# cir23.net
KiCad netlist of a schematic drawn in EAGLE
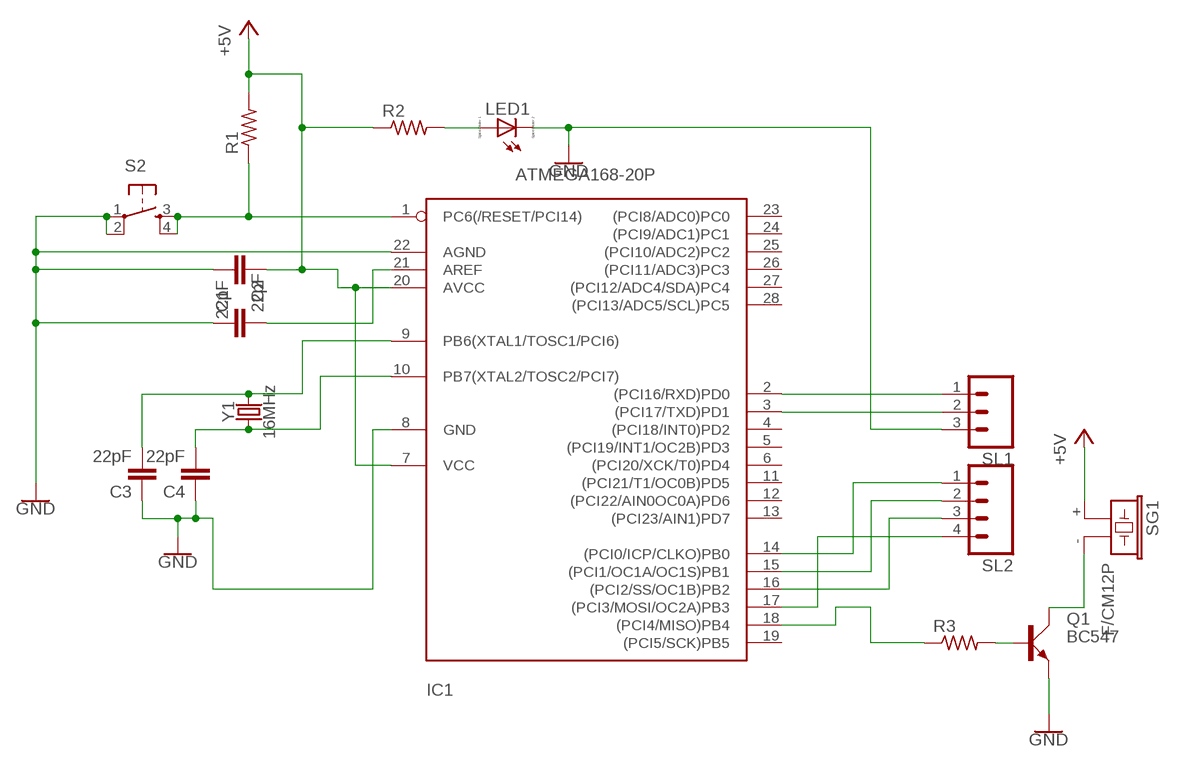
[diagram p0: schematic, sheet 1]

(export (version "E")
  (design (tool "Eeschema 10.0.6"))
  (components
    (comp (ref "C1")
      (value "22pF")
      (footprint "eagle-import:CAP-PTH-2.54")
      (libsource (lib "eagle-import") (part "22PF-PTH-2.54MM-200V-5%"))
    )
    (comp (ref "C2")
      (value "22pF")
      (footprint "eagle-import:CAP-PTH-2.54")
      (libsource (lib "eagle-import") (part "22PF-PTH-2.54MM-200V-5%"))
    )
    (comp (ref "C3")
      (value "22pF")
      (footprint "eagle-import:CAP-PTH-2.54")
      (libsource (lib "eagle-import") (part "22PF-PTH-2.54MM-200V-5%"))
    )
    (comp (ref "C4")
      (value "22pF")
      (footprint "eagle-import:CAP-PTH-2.54")
      (libsource (lib "eagle-import") (part "22PF-PTH-2.54MM-200V-5%"))
    )
    (comp (ref "IC1")
      (value "ATMEGA168-20P")
      (footprint "eagle-import:DIL28-3")
      (libsource (lib "eagle-import") (part "ATMEGA168P-20"))
    )
    (comp (ref "LED1")
      (value "LED_ELD260")
      (footprint "eagle-import:LED_LD260")
      (libsource (lib "eagle-import") (part "LED_ELD260"))
    )
    (comp (ref "Q1")
      (value "BC547")
      (footprint "eagle-import:SOT54A")
      (libsource (lib "eagle-import") (part "BC547"))
    )
    (comp (ref "R1")
      (value "R-US_0204/7")
      (footprint "eagle-import:0204_7")
      (libsource (lib "eagle-import") (part "R-US_0204/7"))
    )
    (comp (ref "R2")
      (value "R-US_0204/7")
      (footprint "eagle-import:0204_7")
      (libsource (lib "eagle-import") (part "R-US_0204/7"))
    )
    (comp (ref "R3")
      (value "R-US_0204/7")
      (footprint "eagle-import:0204_7")
      (libsource (lib "eagle-import") (part "R-US_0204/7"))
    )
    (comp (ref "S2")
      (value "TAC_SWITCHPTH")
      (footprint "eagle-import:TACTILE-PTH")
      (libsource (lib "eagle-import") (part "TAC_SWITCHPTH"))
    )
    (comp (ref "SG1")
      (value "F/CM12P")
      (footprint "eagle-import:F_CM12P")
      (libsource (lib "eagle-import") (part "F/CM12P"))
    )
    (comp (ref "SL1")
      (value "MA03")
      (footprint "eagle-import:03P")
      (libsource (lib "eagle-import") (part "MA03"))
    )
    (comp (ref "SL2")
      (value "MA04")
      (footprint "eagle-import:04PA")
      (libsource (lib "eagle-import") (part "MA04"))
    )
    (comp (ref "Y1")
      (value "16MHz")
      (footprint "eagle-import:HC49US")
      (libsource (lib "eagle-import") (part "CRYSTAL-16MHZPTH-HC49US"))
    )
  )
  (nets
    (net (code "1") (name "+5V") (class "Default")
      (node (ref "C2") (pin "1") (pinfunction "1_1") (pintype "passive"))
      (node (ref "IC1") (pin "20") (pinfunction "AVCC_20") (pintype "bidirectional"))
      (node (ref "IC1") (pin "7") (pinfunction "VCC_7") (pintype "bidirectional"))
      (node (ref "R1") (pin "2") (pinfunction "2_2") (pintype "passive"))
      (node (ref "R2") (pin "1") (pinfunction "1_1") (pintype "passive"))
      (node (ref "SG1") (pin "+") (pinfunction "1_+") (pintype "passive"))
    )
    (net (code "2") (name "GND") (class "Default")
      (node (ref "C1") (pin "1") (pinfunction "1_1") (pintype "passive"))
      (node (ref "C2") (pin "2") (pinfunction "2_2") (pintype "passive"))
      (node (ref "C3") (pin "1") (pinfunction "1_1") (pintype "passive"))
      (node (ref "C4") (pin "1") (pinfunction "1_1") (pintype "passive"))
      (node (ref "IC1") (pin "22") (pinfunction "AGND_22") (pintype "bidirectional"))
      (node (ref "IC1") (pin "8") (pinfunction "GND_8") (pintype "bidirectional"))
      (node (ref "LED1") (pin "K") (pinfunction "C_K") (pintype "passive"))
      (node (ref "Q1") (pin "E") (pinfunction "E_E") (pintype "passive"))
      (node (ref "S2") (pin "1") (pinfunction "1_1") (pintype "passive"))
      (node (ref "S2") (pin "2") (pinfunction "2_2") (pintype "passive"))
      (node (ref "SL1") (pin "3") (pinfunction "3_3") (pintype "passive"))
    )
    (net (code "3") (name "Net-(IC1-(PCI0{slash}ICP{slash}CLKO)PB0)") (class "Default")
      (node (ref "IC1") (pin "14") (pinfunction "(PCI0/ICP/CLKO)PB0_14") (pintype "bidirectional"))
      (node (ref "SL2") (pin "1") (pinfunction "1_1") (pintype "passive"))
    )
    (net (code "4") (name "Net-(IC1-(PCI1{slash}OC1A{slash}OC1S)PB1)") (class "Default")
      (node (ref "IC1") (pin "15") (pinfunction "(PCI1/OC1A/OC1S)PB1_15") (pintype "bidirectional"))
      (node (ref "SL2") (pin "2") (pinfunction "2_2") (pintype "passive"))
    )
    (net (code "5") (name "Net-(IC1-(PCI2{slash}SS{slash}OC1B)PB2)") (class "Default")
      (node (ref "IC1") (pin "16") (pinfunction "(PCI2/SS/OC1B)PB2_16") (pintype "bidirectional"))
      (node (ref "SL2") (pin "3") (pinfunction "3_3") (pintype "passive"))
    )
    (net (code "6") (name "Net-(IC1-(PCI3{slash}MOSI{slash}OC2A)PB3)") (class "Default")
      (node (ref "IC1") (pin "17") (pinfunction "(PCI3/MOSI/OC2A)PB3_17") (pintype "bidirectional"))
      (node (ref "SL2") (pin "4") (pinfunction "4_4") (pintype "passive"))
    )
    (net (code "7") (name "Net-(IC1-(PCI4{slash}MISO)PB4)") (class "Default")
      (node (ref "IC1") (pin "18") (pinfunction "(PCI4/MISO)PB4_18") (pintype "bidirectional"))
      (node (ref "R3") (pin "1") (pinfunction "1_1") (pintype "passive"))
    )
    (net (code "8") (name "Net-(IC1-(PCI16{slash}RXD)PD0)") (class "Default")
      (node (ref "IC1") (pin "2") (pinfunction "(PCI16/RXD)PD0_2") (pintype "bidirectional"))
      (node (ref "SL1") (pin "1") (pinfunction "1_1") (pintype "passive"))
    )
    (net (code "9") (name "Net-(IC1-(PCI17{slash}TXD)PD1)") (class "Default")
      (node (ref "IC1") (pin "3") (pinfunction "(PCI17/TXD)PD1_3") (pintype "bidirectional"))
      (node (ref "SL1") (pin "2") (pinfunction "2_2") (pintype "passive"))
    )
    (net (code "10") (name "Net-(IC1-AREF)") (class "Default")
      (node (ref "C1") (pin "2") (pinfunction "2_2") (pintype "passive"))
      (node (ref "IC1") (pin "21") (pinfunction "AREF_21") (pintype "bidirectional"))
    )
    (net (code "11") (name "Net-(IC1-PB6(XTAL1{slash}TOSC1{slash}PCI6))") (class "Default")
      (node (ref "C3") (pin "2") (pinfunction "2_2") (pintype "passive"))
      (node (ref "IC1") (pin "9") (pinfunction "PB6(XTAL1/TOSC1/PCI6)_9") (pintype "bidirectional"))
      (node (ref "Y1") (pin "2") (pinfunction "2_2") (pintype "passive"))
    )
    (net (code "12") (name "Net-(IC1-PB7(XTAL2{slash}TOSC2{slash}PCI7))") (class "Default")
      (node (ref "C4") (pin "2") (pinfunction "2_2") (pintype "passive"))
      (node (ref "IC1") (pin "10") (pinfunction "PB7(XTAL2/TOSC2/PCI7)_10") (pintype "bidirectional"))
      (node (ref "Y1") (pin "1") (pinfunction "1_1") (pintype "passive"))
    )
    (net (code "13") (name "Net-(IC1-PC6({slash}RESET{slash}PCI14))") (class "Default")
      (node (ref "IC1") (pin "1") (pinfunction "PC6(/RESET/PCI14)_1") (pintype "bidirectional"))
      (node (ref "R1") (pin "1") (pinfunction "1_1") (pintype "passive"))
      (node (ref "S2") (pin "3") (pinfunction "3_3") (pintype "passive"))
      (node (ref "S2") (pin "4") (pinfunction "4_4") (pintype "passive"))
    )
    (net (code "14") (name "Net-(LED1-PadA)") (class "Default")
      (node (ref "LED1") (pin "A") (pinfunction "A_A") (pintype "passive"))
      (node (ref "R2") (pin "2") (pinfunction "2_2") (pintype "passive"))
    )
    (net (code "15") (name "Net-(Q1-PadB)") (class "Default")
      (node (ref "Q1") (pin "B") (pinfunction "B_B") (pintype "passive"))
      (node (ref "R3") (pin "2") (pinfunction "2_2") (pintype "passive"))
    )
    (net (code "16") (name "Net-(SG1-2)") (class "Default")
      (node (ref "Q1") (pin "C") (pinfunction "C_C") (pintype "passive"))
      (node (ref "SG1") (pin "-") (pinfunction "2_-") (pintype "passive"))
    )
    (net (code "17") (name "unconnected-(IC1-(PCI5{slash}SCK)PB5-Pad19)") (class "Default")
      (node (ref "IC1") (pin "19") (pinfunction "(PCI5/SCK)PB5_19") (pintype "bidirectional"))
    )
    (net (code "18") (name "unconnected-(IC1-(PCI8{slash}ADC0)PC0-Pad23)") (class "Default")
      (node (ref "IC1") (pin "23") (pinfunction "(PCI8/ADC0)PC0_23") (pintype "bidirectional"))
    )
    (net (code "19") (name "unconnected-(IC1-(PCI9{slash}ADC1)PC1-Pad24)") (class "Default")
      (node (ref "IC1") (pin "24") (pinfunction "(PCI9/ADC1)PC1_24") (pintype "bidirectional"))
    )
    (net (code "20") (name "unconnected-(IC1-(PCI10{slash}ADC2)PC2-Pad25)") (class "Default")
      (node (ref "IC1") (pin "25") (pinfunction "(PCI10/ADC2)PC2_25") (pintype "bidirectional"))
    )
    (net (code "21") (name "unconnected-(IC1-(PCI11{slash}ADC3)PC3-Pad26)") (class "Default")
      (node (ref "IC1") (pin "26") (pinfunction "(PCI11/ADC3)PC3_26") (pintype "bidirectional"))
    )
    (net (code "22") (name "unconnected-(IC1-(PCI12{slash}ADC4{slash}SDA)PC4-Pad27)") (class "Default")
      (node (ref "IC1") (pin "27") (pinfunction "(PCI12/ADC4/SDA)PC4_27") (pintype "bidirectional"))
    )
    (net (code "23") (name "unconnected-(IC1-(PCI13{slash}ADC5{slash}SCL)PC5-Pad28)") (class "Default")
      (node (ref "IC1") (pin "28") (pinfunction "(PCI13/ADC5/SCL)PC5_28") (pintype "bidirectional"))
    )
    (net (code "24") (name "unconnected-(IC1-(PCI18{slash}INT0)PD2-Pad4)") (class "Default")
      (node (ref "IC1") (pin "4") (pinfunction "(PCI18/INT0)PD2_4") (pintype "bidirectional"))
    )
    (net (code "25") (name "unconnected-(IC1-(PCI19{slash}INT1{slash}OC2B)PD3-Pad5)") (class "Default")
      (node (ref "IC1") (pin "5") (pinfunction "(PCI19/INT1/OC2B)PD3_5") (pintype "bidirectional"))
    )
    (net (code "26") (name "unconnected-(IC1-(PCI20{slash}XCK{slash}T0)PD4-Pad6)") (class "Default")
      (node (ref "IC1") (pin "6") (pinfunction "(PCI20/XCK/T0)PD4_6") (pintype "bidirectional"))
    )
    (net (code "27") (name "unconnected-(IC1-(PCI21{slash}T1{slash}OC0B)PD5-Pad11)") (class "Default")
      (node (ref "IC1") (pin "11") (pinfunction "(PCI21/T1/OC0B)PD5_11") (pintype "bidirectional"))
    )
    (net (code "28") (name "unconnected-(IC1-(PCI22{slash}AIN0OC0A)PD6-Pad12)") (class "Default")
      (node (ref "IC1") (pin "12") (pinfunction "(PCI22/AIN0OC0A)PD6_12") (pintype "bidirectional"))
    )
    (net (code "29") (name "unconnected-(IC1-(PCI23{slash}AIN1)PD7-Pad13)") (class "Default")
      (node (ref "IC1") (pin "13") (pinfunction "(PCI23/AIN1)PD7_13") (pintype "bidirectional"))
    )
  )
)
